# HAB1_Schematic.net
KiCad netlist of a schematic drawn in EAGLE
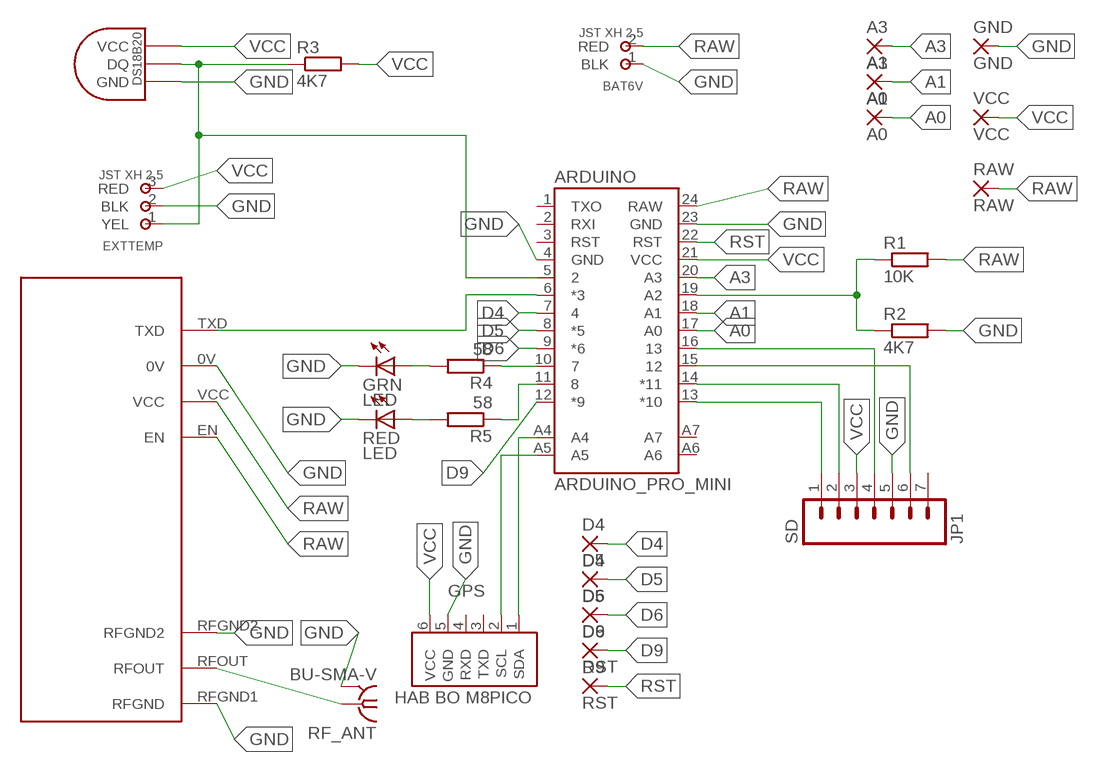
[diagram p0: schematic, sheet 1]

(export (version "E")
  (design (tool "Eeschema 10.0.6"))
  (components
    (comp (ref "A0")
      (value "A0")
      (footprint "eagle-import:1,6_0,8")
      (libsource (lib "eagle-import") (part "1,6/0,8"))
    )
    (comp (ref "A1")
      (value "A1")
      (footprint "eagle-import:1,6_0,8")
      (libsource (lib "eagle-import") (part "1,6/0,8"))
    )
    (comp (ref "A3")
      (value "A3")
      (footprint "eagle-import:1,6_0,8")
      (libsource (lib "eagle-import") (part "1,6/0,8"))
    )
    (comp (ref "ARDUINO")
      (value "ARDUINO_PRO_MINI")
      (footprint "eagle-import:ARDUINO_PRO_MINI")
      (libsource (lib "eagle-import") (part "ARDUINO_PRO_MINI"))
    )
    (comp (ref "BAT6V")
      (value "JST-XH-2.5-2PIN-MAIL")
      (footprint "eagle-import:JST-XH-2.5-2PIN-MAILE")
      (libsource (lib "eagle-import") (part "JST-XH-2.5-2PIN-MAIL"))
    )
    (comp (ref "D4")
      (value "D4")
      (footprint "eagle-import:1,6_0,8")
      (libsource (lib "eagle-import") (part "1,6/0,8"))
    )
    (comp (ref "D5")
      (value "D5")
      (footprint "eagle-import:1,6_0,8")
      (libsource (lib "eagle-import") (part "1,6/0,8"))
    )
    (comp (ref "D6")
      (value "D6")
      (footprint "eagle-import:1,6_0,8")
      (libsource (lib "eagle-import") (part "1,6/0,8"))
    )
    (comp (ref "D9")
      (value "D9")
      (footprint "eagle-import:1,6_0,8")
      (libsource (lib "eagle-import") (part "1,6/0,8"))
    )
    (comp (ref "EXTTEMP")
      (value "JST-XH-2.5-2PIN-MAIL")
      (footprint "eagle-import:JST-XH-2.5-2PIN-MAILE")
      (libsource (lib "eagle-import") (part "JST XH 2.5 3 Pin Male_JST-XH-2.5-2PIN-MAIL"))
    )
    (comp (ref "GND")
      (value "GND")
      (footprint "eagle-import:1,6_0,8")
      (libsource (lib "eagle-import") (part "1,6/0,8"))
    )
    (comp (ref "GPS")
      (value "HAB-BO-M8PICONORMAL")
      (footprint "eagle-import:HAB-BO-M8PICO")
      (libsource (lib "eagle-import") (part "HAB-BO-M8PICONORMAL"))
    )
    (comp (ref "GRN")
      (value "LED")
      (footprint "eagle-import:LED3MM")
      (libsource (lib "eagle-import") (part "LED3MM"))
    )
    (comp (ref "INT")
      (value "DS1820TO92")
      (footprint "eagle-import:DS1820")
      (libsource (lib "eagle-import") (part "DS1820TO92"))
    )
    (comp (ref "JP1")
      (value "SD")
      (footprint "eagle-import:1X07")
      (libsource (lib "eagle-import") (part "M07"))
    )
    (comp (ref "R1")
      (value "10K")
      (footprint "eagle-import:0204_5")
      (libsource (lib "eagle-import") (part "R-EU_0204/5"))
    )
    (comp (ref "R2")
      (value "4K7")
      (footprint "eagle-import:0204_5")
      (libsource (lib "eagle-import") (part "R-EU_0204/5"))
    )
    (comp (ref "R3")
      (value "4K7")
      (footprint "eagle-import:0204_5")
      (libsource (lib "eagle-import") (part "R-EU_0204/5"))
    )
    (comp (ref "R4")
      (value "58")
      (footprint "eagle-import:0204_5")
      (libsource (lib "eagle-import") (part "R-EU_0204/5"))
    )
    (comp (ref "R5")
      (value "58")
      (footprint "eagle-import:0204_5")
      (libsource (lib "eagle-import") (part "R-EU_0204/5"))
    )
    (comp (ref "RAW")
      (value "RAW")
      (footprint "eagle-import:1,6_0,8")
      (libsource (lib "eagle-import") (part "1,6/0,8"))
    )
    (comp (ref "RED")
      (value "LED")
      (footprint "eagle-import:LED3MM")
      (libsource (lib "eagle-import") (part "LED3MM"))
    )
    (comp (ref "RF_ANT")
      (value "BU-SMA-V")
      (footprint "eagle-import:BU-SMA-V")
      (libsource (lib "eagle-import") (part "BU-SMA-V"))
    )
    (comp (ref "RST")
      (value "RST")
      (footprint "eagle-import:1,6_0,8")
      (libsource (lib "eagle-import") (part "1,6/0,8"))
    )
    (comp (ref "U$3")
      (value "NTX2-VERTICAL")
      (footprint "eagle-import:NTX2-VERTICAL")
      (libsource (lib "eagle-import") (part "NTX2-VERTICAL"))
    )
    (comp (ref "VCC")
      (value "VCC")
      (footprint "eagle-import:1,6_0,8")
      (libsource (lib "eagle-import") (part "1,6/0,8"))
    )
  )
  (nets
    (net (code "1") (name "A0") (class "Default")
      (node (ref "A0") (pin "1") (pinfunction "P_1") (pintype "passive"))
      (node (ref "ARDUINO") (pin "17") (pinfunction "A0_17") (pintype "bidirectional"))
    )
    (net (code "2") (name "A1") (class "Default")
      (node (ref "A1") (pin "1") (pinfunction "P_1") (pintype "passive"))
      (node (ref "ARDUINO") (pin "18") (pinfunction "A1_18") (pintype "bidirectional"))
    )
    (net (code "3") (name "A3") (class "Default")
      (node (ref "A3") (pin "1") (pinfunction "P_1") (pintype "passive"))
      (node (ref "ARDUINO") (pin "20") (pinfunction "A3_20") (pintype "bidirectional"))
    )
    (net (code "4") (name "D4") (class "Default")
      (node (ref "ARDUINO") (pin "7") (pinfunction "4_7") (pintype "bidirectional"))
      (node (ref "D4") (pin "1") (pinfunction "P_1") (pintype "passive"))
    )
    (net (code "5") (name "D5") (class "Default")
      (node (ref "ARDUINO") (pin "8") (pinfunction "*5_8") (pintype "bidirectional"))
      (node (ref "D5") (pin "1") (pinfunction "P_1") (pintype "passive"))
    )
    (net (code "6") (name "D6") (class "Default")
      (node (ref "ARDUINO") (pin "9") (pinfunction "*6_9") (pintype "bidirectional"))
      (node (ref "D6") (pin "1") (pinfunction "P_1") (pintype "passive"))
    )
    (net (code "7") (name "D9") (class "Default")
      (node (ref "ARDUINO") (pin "12") (pinfunction "*9_12") (pintype "bidirectional"))
      (node (ref "D9") (pin "1") (pinfunction "P_1") (pintype "passive"))
    )
    (net (code "8") (name "GND") (class "Default")
      (node (ref "ARDUINO") (pin "23") (pinfunction "GND_23") (pintype "bidirectional"))
      (node (ref "ARDUINO") (pin "4") (pinfunction "GND_4") (pintype "bidirectional"))
      (node (ref "BAT6V") (pin "1") (pinfunction "BLK_1") (pintype "bidirectional"))
      (node (ref "EXTTEMP") (pin "2") (pinfunction "BLK_2") (pintype "bidirectional"))
      (node (ref "GND") (pin "1") (pinfunction "P_1") (pintype "passive"))
      (node (ref "GPS") (pin "5") (pinfunction "GND_5") (pintype "bidirectional"))
      (node (ref "GRN") (pin "K") (pinfunction "C_K") (pintype "passive"))
      (node (ref "INT") (pin "GND") (pinfunction "GND_GND") (pintype "power_in"))
      (node (ref "JP1") (pin "5") (pinfunction "5_5") (pintype "passive"))
      (node (ref "R2") (pin "2") (pinfunction "2_2") (pintype "passive"))
      (node (ref "RED") (pin "K") (pinfunction "C_K") (pintype "passive"))
      (node (ref "RF_ANT") (pin "2") (pinfunction "2_2") (pintype "passive"))
      (node (ref "RF_ANT") (pin "3") (pinfunction "2_3") (pintype "passive"))
      (node (ref "RF_ANT") (pin "4") (pinfunction "2_4") (pintype "passive"))
      (node (ref "RF_ANT") (pin "5") (pinfunction "2_5") (pintype "passive"))
      (node (ref "U$3") (pin "0V") (pinfunction "0V_0V") (pintype "bidirectional"))
      (node (ref "U$3") (pin "RFGND1") (pinfunction "RFGND_RFGND1") (pintype "bidirectional"))
      (node (ref "U$3") (pin "RFGND2") (pinfunction "RFGND2_RFGND2") (pintype "bidirectional"))
    )
    (net (code "9") (name "Net-(ARDUINO-*3)") (class "Default")
      (node (ref "ARDUINO") (pin "6") (pinfunction "*3_6") (pintype "bidirectional"))
      (node (ref "U$3") (pin "TXD") (pinfunction "TXD_TXD") (pintype "bidirectional"))
    )
    (net (code "10") (name "Net-(ARDUINO-*10)") (class "Default")
      (node (ref "ARDUINO") (pin "13") (pinfunction "*10_13") (pintype "bidirectional"))
      (node (ref "JP1") (pin "1") (pinfunction "1_1") (pintype "passive"))
    )
    (net (code "11") (name "Net-(ARDUINO-*11)") (class "Default")
      (node (ref "ARDUINO") (pin "14") (pinfunction "*11_14") (pintype "bidirectional"))
      (node (ref "JP1") (pin "2") (pinfunction "2_2") (pintype "passive"))
    )
    (net (code "12") (name "Net-(ARDUINO-2)") (class "Default")
      (node (ref "ARDUINO") (pin "5") (pinfunction "2_5") (pintype "bidirectional"))
      (node (ref "EXTTEMP") (pin "1") (pinfunction "YEL_1") (pintype "bidirectional"))
      (node (ref "INT") (pin "DQ") (pinfunction "DQ_DQ") (pintype "bidirectional"))
      (node (ref "R3") (pin "1") (pinfunction "1_1") (pintype "passive"))
    )
    (net (code "13") (name "Net-(ARDUINO-7)") (class "Default")
      (node (ref "ARDUINO") (pin "10") (pinfunction "7_10") (pintype "bidirectional"))
      (node (ref "R4") (pin "1") (pinfunction "1_1") (pintype "passive"))
    )
    (net (code "14") (name "Net-(ARDUINO-8)") (class "Default")
      (node (ref "ARDUINO") (pin "11") (pinfunction "8_11") (pintype "bidirectional"))
      (node (ref "R5") (pin "1") (pinfunction "1_1") (pintype "passive"))
    )
    (net (code "15") (name "Net-(ARDUINO-12)") (class "Default")
      (node (ref "ARDUINO") (pin "15") (pinfunction "12_15") (pintype "bidirectional"))
      (node (ref "JP1") (pin "6") (pinfunction "6_6") (pintype "passive"))
    )
    (net (code "16") (name "Net-(ARDUINO-13)") (class "Default")
      (node (ref "ARDUINO") (pin "16") (pinfunction "13_16") (pintype "bidirectional"))
      (node (ref "JP1") (pin "4") (pinfunction "4_4") (pintype "passive"))
    )
    (net (code "17") (name "Net-(ARDUINO-A2)") (class "Default")
      (node (ref "ARDUINO") (pin "19") (pinfunction "A2_19") (pintype "bidirectional"))
      (node (ref "R1") (pin "1") (pinfunction "1_1") (pintype "passive"))
      (node (ref "R2") (pin "1") (pinfunction "1_1") (pintype "passive"))
    )
    (net (code "18") (name "Net-(GPS-SCL)") (class "Default")
      (node (ref "ARDUINO") (pin "A5") (pinfunction "A5_A5") (pintype "bidirectional"))
      (node (ref "GPS") (pin "2") (pinfunction "SCL_2") (pintype "bidirectional"))
    )
    (net (code "19") (name "Net-(GPS-SDA)") (class "Default")
      (node (ref "ARDUINO") (pin "A4") (pinfunction "A4_A4") (pintype "bidirectional"))
      (node (ref "GPS") (pin "1") (pinfunction "SDA_1") (pintype "bidirectional"))
    )
    (net (code "20") (name "Net-(GRN-PadA)") (class "Default")
      (node (ref "GRN") (pin "A") (pinfunction "A_A") (pintype "passive"))
      (node (ref "R4") (pin "2") (pinfunction "2_2") (pintype "passive"))
    )
    (net (code "21") (name "Net-(R5-Pad2)") (class "Default")
      (node (ref "R5") (pin "2") (pinfunction "2_2") (pintype "passive"))
      (node (ref "RED") (pin "A") (pinfunction "A_A") (pintype "passive"))
    )
    (net (code "22") (name "Net-(RF_ANT-Pad1)") (class "Default")
      (node (ref "RF_ANT") (pin "1") (pinfunction "1_1") (pintype "passive"))
      (node (ref "U$3") (pin "RFOUT") (pinfunction "RFOUT_RFOUT") (pintype "bidirectional"))
    )
    (net (code "23") (name "RAW") (class "Default")
      (node (ref "ARDUINO") (pin "24") (pinfunction "RAW_24") (pintype "bidirectional"))
      (node (ref "BAT6V") (pin "2") (pinfunction "RED_2") (pintype "bidirectional"))
      (node (ref "R1") (pin "2") (pinfunction "2_2") (pintype "passive"))
      (node (ref "RAW") (pin "1") (pinfunction "P_1") (pintype "passive"))
      (node (ref "U$3") (pin "EN") (pinfunction "EN_EN") (pintype "bidirectional"))
      (node (ref "U$3") (pin "VCC") (pinfunction "VCC_VCC") (pintype "bidirectional"))
    )
    (net (code "24") (name "RST") (class "Default")
      (node (ref "ARDUINO") (pin "22") (pinfunction "RST_22") (pintype "bidirectional"))
      (node (ref "RST") (pin "1") (pinfunction "P_1") (pintype "passive"))
    )
    (net (code "25") (name "VCC") (class "Default")
      (node (ref "ARDUINO") (pin "21") (pinfunction "VCC_21") (pintype "bidirectional"))
      (node (ref "EXTTEMP") (pin "3") (pinfunction "RED_3") (pintype "bidirectional"))
      (node (ref "GPS") (pin "6") (pinfunction "VCC_6") (pintype "bidirectional"))
      (node (ref "INT") (pin "VDD") (pinfunction "VCC_VDD") (pintype "power_in"))
      (node (ref "JP1") (pin "3") (pinfunction "3_3") (pintype "passive"))
      (node (ref "R3") (pin "2") (pinfunction "2_2") (pintype "passive"))
      (node (ref "VCC") (pin "1") (pinfunction "P_1") (pintype "passive"))
    )
    (net (code "26") (name "unconnected-(ARDUINO-PadA6)") (class "Default")
      (node (ref "ARDUINO") (pin "A6") (pinfunction "A6_A6") (pintype "bidirectional"))
    )
    (net (code "27") (name "unconnected-(ARDUINO-PadA7)") (class "Default")
      (node (ref "ARDUINO") (pin "A7") (pinfunction "A7_A7") (pintype "bidirectional"))
    )
    (net (code "28") (name "unconnected-(ARDUINO-RST-Pad3)") (class "Default")
      (node (ref "ARDUINO") (pin "3") (pinfunction "RST_3") (pintype "bidirectional"))
    )
    (net (code "29") (name "unconnected-(ARDUINO-RXI-Pad2)") (class "Default")
      (node (ref "ARDUINO") (pin "2") (pinfunction "RXI_2") (pintype "bidirectional"))
    )
    (net (code "30") (name "unconnected-(ARDUINO-TXO-Pad1)") (class "Default")
      (node (ref "ARDUINO") (pin "1") (pinfunction "TXO_1") (pintype "bidirectional"))
    )
    (net (code "31") (name "unconnected-(GPS-RXD-Pad4)") (class "Default")
      (node (ref "GPS") (pin "4") (pinfunction "RXD_4") (pintype "bidirectional"))
    )
    (net (code "32") (name "unconnected-(GPS-TXD-Pad3)") (class "Default")
      (node (ref "GPS") (pin "3") (pinfunction "TXD_3") (pintype "bidirectional"))
    )
    (net (code "33") (name "unconnected-(JP1-Pad7)") (class "Default")
      (node (ref "JP1") (pin "7") (pinfunction "7_7") (pintype "passive"))
    )
  )
)
